# POWER.net
KiCad netlist of a schematic drawn in Altium Designer
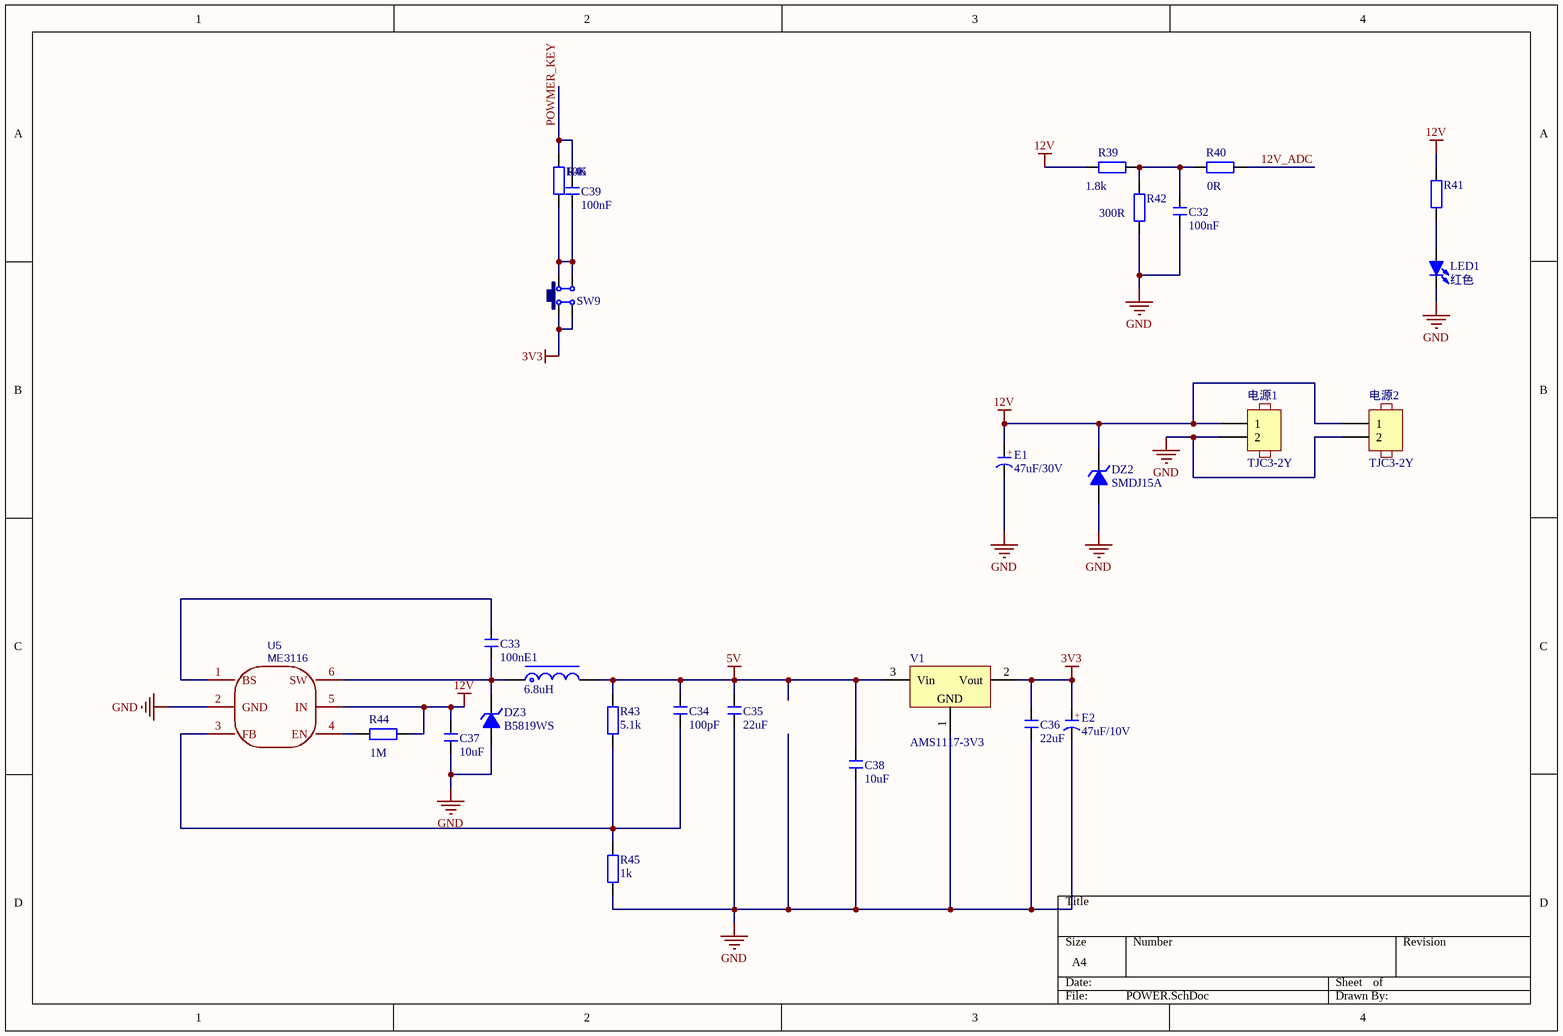
[diagram p0: POWER.SchDoc]

(export (version "E")
  (design (tool "Eeschema 10.0.6"))
  (components
    (comp (ref "C32")
      (value "100nF")
      (footprint "C 0805_L")
      (description "无极性贴片电容")
      (fields (field (name "版权归属") "源创客"))
      (libsource (lib "3.1   - 电阻-电容-电感") (part "C"))
    )
    (comp (ref "C33")
      (value "100nF")
      (footprint "C 0805_L")
      (description "无极性贴片电容")
      (fields (field (name "版权归属") "源创客"))
      (libsource (lib "3.1   - 电阻-电容-电感") (part "C"))
    )
    (comp (ref "C34")
      (value "100pF")
      (footprint "C 0805_L")
      (description "无极性贴片电容")
      (fields (field (name "版权归属") "源创客"))
      (libsource (lib "3.1   - 电阻-电容-电感") (part "C"))
    )
    (comp (ref "C35")
      (value "22uF")
      (footprint "C 0805_L")
      (description "无极性贴片电容")
      (fields (field (name "版权归属") "源创客"))
      (libsource (lib "3.1   - 电阻-电容-电感") (part "C"))
    )
    (comp (ref "C36")
      (value "22uF")
      (footprint "C 0805_L")
      (description "无极性贴片电容")
      (fields (field (name "版权归属") "源创客"))
      (libsource (lib "3.1   - 电阻-电容-电感") (part "C"))
    )
    (comp (ref "C37")
      (value "10uF")
      (footprint "C 0805_L")
      (description "无极性贴片电容")
      (fields (field (name "版权归属") "源创客"))
      (libsource (lib "3.1   - 电阻-电容-电感") (part "C"))
    )
    (comp (ref "C38")
      (value "10uF")
      (footprint "C 0805_L")
      (description "无极性贴片电容")
      (fields (field (name "版权归属") "源创客"))
      (libsource (lib "3.1   - 电阻-电容-电感") (part "C"))
    )
    (comp (ref "C39")
      (value "100nF")
      (footprint "C 0603_L")
      (description "无极性贴片电容")
      (fields (field (name "版权归属") "源创客"))
      (libsource (lib "3.1   - 电阻-电容-电感") (part "C"))
    )
    (comp (ref "DZ2")
      (value "SMDJ15A")
      (footprint "SMC")
      (description "TVS 15V截止 峰值浪涌电流：123A                   C438153")
      (fields (field (name "版权归属") "源创客"))
      (libsource (lib "8.1   - 二极管-整流桥") (part "1N4106"))
    )
    (comp (ref "DZ3")
      (value "B5819WS")
      (footprint "SOD-323")
      (description "电压:40V 电流:1A                                C7420331")
      (fields (field (name "版权归属") "源创客"))
      (libsource (lib "8.1   - 二极管-整流桥") (part "1N5256"))
    )
    (comp (ref "E1")
      (value "47uF/30V")
      (footprint "CM D(6.3*7.7)")
      (description "JVJ50V47M6x8                        47uF ±20% 50V                            C46550421")
      (fields (field (name "版权归属") "源创客"))
      (libsource (lib "3.1   - 电阻-电容-电感") (part "C-CS"))
    )
    (comp (ref "E2")
      (value "47uF/10V")
      (footprint "CM B(4*5.4)")
      (description "47uF ±20% 10V                           C48970978")
      (fields (field (name "版权归属") "源创客"))
      (libsource (lib "3.1   - 电阻-电容-电感") (part "C-CS"))
    )
    (comp (ref "L1")
      (value "6.8uH")
      (footprint "CD42")
      (description "YP0402-6R8M                          C576569")
      (fields (field (name "版权归属") "源创客"))
      (libsource (lib "3.1   - 电阻-电容-电感") (part "L-CD"))
    )
    (comp (ref "LED1")
      (value "红色")
      (footprint "LED 0805R")
      (description "贴片LED")
      (fields (field (name "版权归属") "源创客"))
      (libsource (lib "9.1   - LED") (part "LED-SMD"))
    )
    (comp (ref "R39")
      (value "1.8k")
      (footprint "R 0805_L")
      (description "贴片电阻")
      (fields (field (name "版权归属") "源创客"))
      (libsource (lib "3.1   - 电阻-电容-电感") (part "R"))
    )
    (comp (ref "R40")
      (value "0R")
      (footprint "R 0805_L")
      (description "贴片电阻")
      (fields (field (name "版权归属") "源创客"))
      (libsource (lib "3.1   - 电阻-电容-电感") (part "R"))
    )
    (comp (ref "R41")
      (value "~")
      (footprint "R 0805_L")
      (description "贴片电阻")
      (fields (field (name "版权归属") "源创客"))
      (libsource (lib "3.1   - 电阻-电容-电感") (part "R"))
    )
    (comp (ref "R42")
      (value "300R")
      (footprint "R 0805_L")
      (description "贴片电阻")
      (fields (field (name "版权归属") "源创客"))
      (libsource (lib "3.1   - 电阻-电容-电感") (part "R"))
    )
    (comp (ref "R43")
      (value "5.1k")
      (footprint "R 0805_L")
      (description "贴片电阻")
      (fields (field (name "版权归属") "源创客"))
      (libsource (lib "3.1   - 电阻-电容-电感") (part "R"))
    )
    (comp (ref "R44")
      (value "1M")
      (footprint "R 0805_L")
      (description "贴片电阻")
      (fields (field (name "版权归属") "源创客"))
      (libsource (lib "3.1   - 电阻-电容-电感") (part "R"))
    )
    (comp (ref "R45")
      (value "1k")
      (footprint "R 0805_L")
      (description "贴片电阻")
      (fields (field (name "版权归属") "源创客"))
      (libsource (lib "3.1   - 电阻-电容-电感") (part "R"))
    )
    (comp (ref "R46")
      (value "10K")
      (footprint "R 0603_L")
      (description "贴片电阻")
      (fields (field (name "版权归属") "源创客"))
      (libsource (lib "3.1   - 电阻-电容-电感") (part "R"))
    )
    (comp (ref "SW9")
      (value "6x6x5")
      (footprint "Model Name")
      (description "KH-6X6X5H-STM     C2837531")
      (fields (field (name "版权归属") "源创客"))
      (libsource (lib "5.1   - 按键-开关") (part "TSW SMD-6x6"))
    )
    (comp (ref "U5")
      (value "ME3116")
      (footprint "SOT23-6")
      (fields (field (name "MANUFACTURER") "MICRONE(南京微盟)") (field (name "MANUFACTURER PART") "ME3116AM6G"))
      (libsource (lib "altium-import") (part "root_0_ME3116_"))
    )
    (comp (ref "V1")
      (value "AMS1117-3V3")
      (footprint "SOT-223")
      (description "三端稳压芯片")
      (fields (field (name "版权归属") "源创客"))
      (libsource (lib "1.3   - 电源类芯片") (part "AMS1117"))
    )
    (comp (ref "电源1")
      (value "TJC3-2Y")
      (footprint "MX 1.25-WS-2P")
      (fields (field (name "PUBLISHER") "Altium Limited"))
      (libsource (lib "接口与插座") (part "TJC3-2Y"))
    )
    (comp (ref "电源2")
      (value "TJC3-2Y")
      (footprint "MX 1.25-WS-2P")
      (fields (field (name "PUBLISHER") "Altium Limited"))
      (libsource (lib "接口与插座") (part "TJC3-2Y"))
    )
  )
  (nets
    (net (code "1") (name "/12V_ADC") (class "Default")
      (node (ref "R40") (pin "2") (pinfunction "2_2") (pintype "passive"))
    )
    (net (code "2") (name "/POWMER_KEY") (class "Default")
      (node (ref "C39") (pin "2") (pinfunction "2_2") (pintype "passive"))
      (node (ref "R46") (pin "1") (pinfunction "1_1") (pintype "passive"))
    )
    (net (code "3") (name "3V3") (class "Default")
      (node (ref "C36") (pin "2") (pinfunction "2_2") (pintype "passive"))
      (node (ref "E2") (pin "1") (pinfunction "A_1") (pintype "passive"))
      (node (ref "SW9") (pin "1") (pinfunction "1_1") (pintype "passive"))
      (node (ref "SW9") (pin "4") (pinfunction "4_4") (pintype "passive"))
      (node (ref "V1") (pin "2") (pinfunction "Vout_2") (pintype "passive"))
    )
    (net (code "4") (name "5V") (class "Default")
      (node (ref "C34") (pin "2") (pinfunction "2_2") (pintype "passive"))
      (node (ref "C35") (pin "2") (pinfunction "2_2") (pintype "passive"))
      (node (ref "C38") (pin "2") (pinfunction "2_2") (pintype "passive"))
      (node (ref "L1") (pin "2") (pinfunction "2_2") (pintype "passive"))
      (node (ref "R43") (pin "2") (pinfunction "2_2") (pintype "passive"))
      (node (ref "V1") (pin "3") (pinfunction "Vin_3") (pintype "passive"))
    )
    (net (code "5") (name "12V") (class "Default")
      (node (ref "C37") (pin "2") (pinfunction "2_2") (pintype "passive"))
      (node (ref "DZ2") (pin "2") (pinfunction "K_2") (pintype "passive"))
      (node (ref "E1") (pin "1") (pinfunction "A_1") (pintype "passive"))
      (node (ref "R39") (pin "2") (pinfunction "2_2") (pintype "passive"))
      (node (ref "R41") (pin "1") (pinfunction "1_1") (pintype "passive"))
      (node (ref "R44") (pin "1") (pinfunction "1_1") (pintype "passive"))
      (node (ref "U5") (pin "5") (pinfunction "IN_5") (pintype "passive"))
      (node (ref "电源1") (pin "1") (pinfunction "1_1") (pintype "passive"))
      (node (ref "电源2") (pin "1") (pinfunction "1_1") (pintype "passive"))
    )
    (net (code "6") (name "GND") (class "Default")
      (node (ref "C32") (pin "1") (pinfunction "1_1") (pintype "passive"))
      (node (ref "C35") (pin "1") (pinfunction "1_1") (pintype "passive"))
      (node (ref "C36") (pin "1") (pinfunction "1_1") (pintype "passive"))
      (node (ref "C37") (pin "1") (pinfunction "1_1") (pintype "passive"))
      (node (ref "C38") (pin "1") (pinfunction "1_1") (pintype "passive"))
      (node (ref "DZ2") (pin "1") (pinfunction "A_1") (pintype "passive"))
      (node (ref "DZ3") (pin "1") (pinfunction "A_1") (pintype "passive"))
      (node (ref "E1") (pin "2") (pinfunction "K_2") (pintype "passive"))
      (node (ref "E2") (pin "2") (pinfunction "K_2") (pintype "passive"))
      (node (ref "LED1") (pin "2") (pinfunction "K_2") (pintype "passive"))
      (node (ref "R42") (pin "2") (pinfunction "2_2") (pintype "passive"))
      (node (ref "R45") (pin "1") (pinfunction "1_1") (pintype "passive"))
      (node (ref "U5") (pin "2") (pinfunction "GND_2") (pintype "passive"))
      (node (ref "V1") (pin "1") (pinfunction "GND_1") (pintype "passive"))
      (node (ref "电源1") (pin "2") (pinfunction "2_2") (pintype "passive"))
      (node (ref "电源2") (pin "2") (pinfunction "2_2") (pintype "passive"))
    )
    (net (code "7") (name "Net-(C32-Pad2)") (class "Default")
      (node (ref "C32") (pin "2") (pinfunction "2_2") (pintype "passive"))
      (node (ref "R39") (pin "1") (pinfunction "1_1") (pintype "passive"))
      (node (ref "R40") (pin "1") (pinfunction "1_1") (pintype "passive"))
      (node (ref "R42") (pin "1") (pinfunction "1_1") (pintype "passive"))
    )
    (net (code "8") (name "Net-(C39-Pad1)") (class "Default")
      (node (ref "C39") (pin "1") (pinfunction "1_1") (pintype "passive"))
      (node (ref "R46") (pin "2") (pinfunction "2_2") (pintype "passive"))
      (node (ref "SW9") (pin "2") (pinfunction "2_2") (pintype "passive"))
      (node (ref "SW9") (pin "3") (pinfunction "3_3") (pintype "passive"))
    )
    (net (code "9") (name "Net-(DZ3-K)") (class "Default")
      (node (ref "C33") (pin "1") (pinfunction "1_1") (pintype "passive"))
      (node (ref "DZ3") (pin "2") (pinfunction "K_2") (pintype "passive"))
      (node (ref "L1") (pin "1") (pinfunction "1_1") (pintype "passive"))
      (node (ref "U5") (pin "6") (pinfunction "SW_6") (pintype "passive"))
    )
    (net (code "10") (name "Net-(LED1-A)") (class "Default")
      (node (ref "LED1") (pin "1") (pinfunction "A_1") (pintype "passive"))
      (node (ref "R41") (pin "2") (pinfunction "2_2") (pintype "passive"))
    )
    (net (code "11") (name "Net-(U5-BS)") (class "Default")
      (node (ref "C33") (pin "2") (pinfunction "2_2") (pintype "passive"))
      (node (ref "U5") (pin "1") (pinfunction "BS_1") (pintype "passive"))
    )
    (net (code "12") (name "Net-(U5-EN)") (class "Default")
      (node (ref "R44") (pin "2") (pinfunction "2_2") (pintype "passive"))
      (node (ref "U5") (pin "4") (pinfunction "EN_4") (pintype "passive"))
    )
    (net (code "13") (name "Net-(U5-FB)") (class "Default")
      (node (ref "C34") (pin "1") (pinfunction "1_1") (pintype "passive"))
      (node (ref "R43") (pin "1") (pinfunction "1_1") (pintype "passive"))
      (node (ref "R45") (pin "2") (pinfunction "2_2") (pintype "passive"))
      (node (ref "U5") (pin "3") (pinfunction "FB_3") (pintype "passive"))
    )
  )
)
